# bxdrone.net
KiCad netlist of a schematic drawn in EAGLE
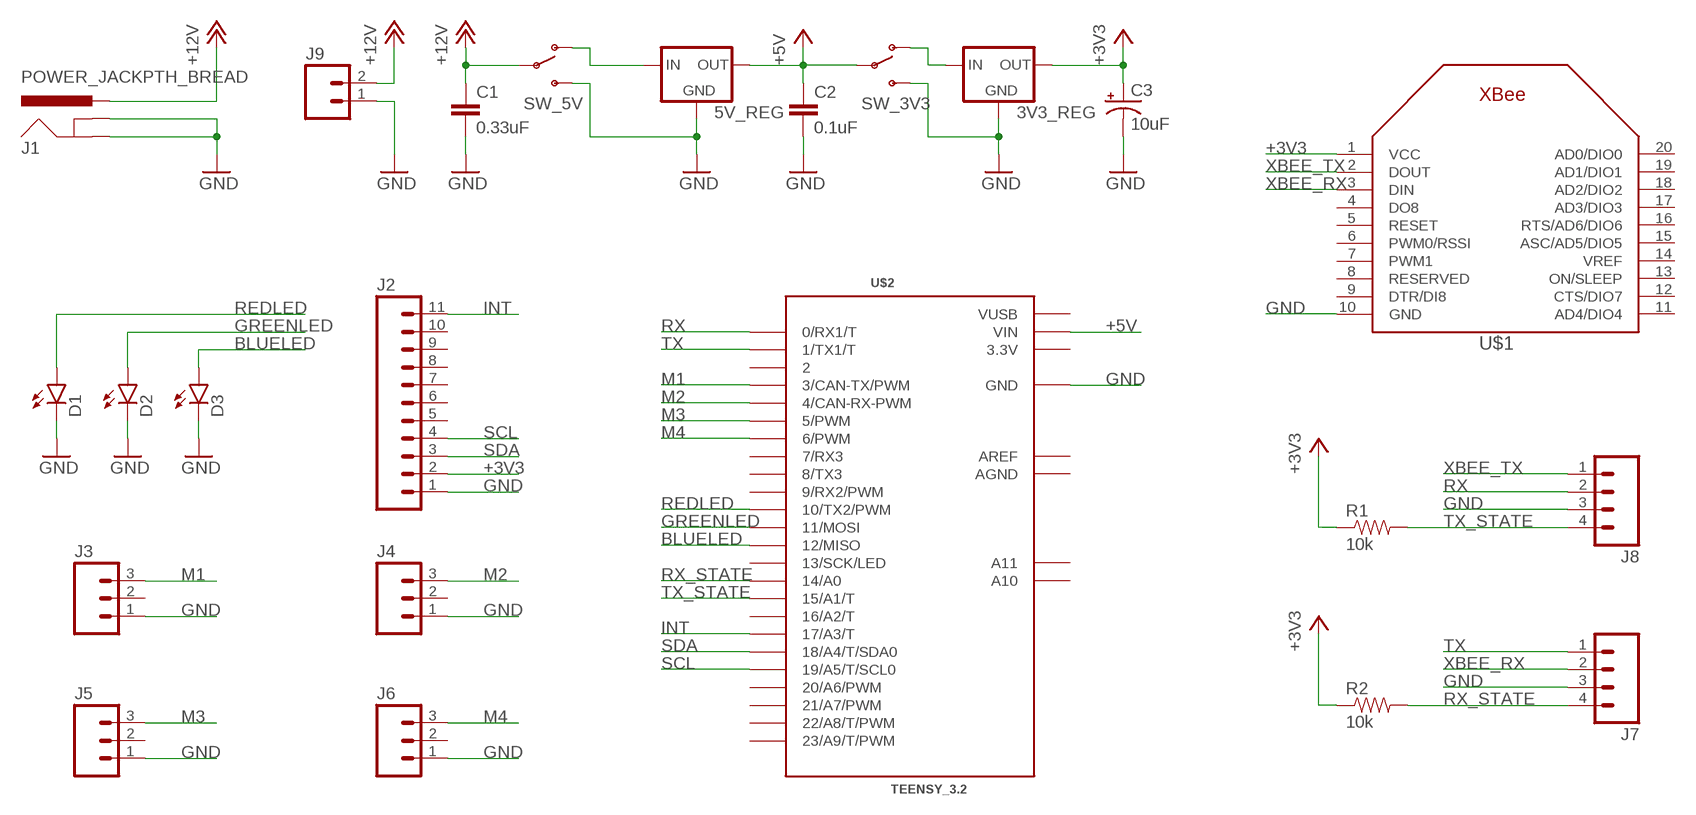
[diagram p0: schematic, sheet 1]

(export (version "E")
  (design (tool "Eeschema 10.0.6"))
  (components
    (comp (ref "3V3_REG")
      (value "LD1117V33")
      (footprint "eagle-import:TO-220-STANDING")
      (fields (field (name "MANUFACTURER") "ST Microelectronics"))
      (libsource (lib "eagle-import") (part "LD1117V33"))
    )
    (comp (ref "5V_REG")
      (value "L78S05CV")
      (footprint "eagle-import:TO-220-STANDING")
      (fields (field (name "MANUFACTURER") "St Microelectronics"))
      (libsource (lib "eagle-import") (part "L78S05CV"))
    )
    (comp (ref "C1")
      (value "0.33uF")
      (footprint "eagle-import:CAP-PTH-SMALL")
      (libsource (lib "eagle-import") (part "CAPPTH"))
    )
    (comp (ref "C2")
      (value "0.1uF")
      (footprint "eagle-import:CAP-PTH-SMALL")
      (libsource (lib "eagle-import") (part "CAPPTH"))
    )
    (comp (ref "C3")
      (value "10uF")
      (footprint "eagle-import:CPOL-RADIAL-10UF-25V")
      (libsource (lib "eagle-import") (part "CAP_POLPTH2"))
    )
    (comp (ref "D1")
      (value "LED5MM")
      (footprint "eagle-import:LED5MM")
      (libsource (lib "eagle-import") (part "LED5MM"))
    )
    (comp (ref "D2")
      (value "LED5MM")
      (footprint "eagle-import:LED5MM")
      (libsource (lib "eagle-import") (part "LED5MM"))
    )
    (comp (ref "D3")
      (value "LED5MM")
      (footprint "eagle-import:LED5MM")
      (libsource (lib "eagle-import") (part "LED5MM"))
    )
    (comp (ref "J1")
      (value "POWER_JACKPTH_BREAD")
      (footprint "eagle-import:POWER_JACK_PTH_BREAD")
      (libsource (lib "eagle-import") (part "POWER_JACKPTH_BREAD"))
    )
    (comp (ref "J2")
      (value "M11PTH")
      (footprint "eagle-import:1X11")
      (libsource (lib "eagle-import") (part "M11PTH"))
    )
    (comp (ref "J3")
      (value "M03PTH")
      (footprint "eagle-import:1X03")
      (libsource (lib "eagle-import") (part "M03PTH"))
    )
    (comp (ref "J4")
      (value "M03PTH")
      (footprint "eagle-import:1X03")
      (libsource (lib "eagle-import") (part "M03PTH"))
    )
    (comp (ref "J5")
      (value "M03PTH")
      (footprint "eagle-import:1X03")
      (libsource (lib "eagle-import") (part "M03PTH"))
    )
    (comp (ref "J6")
      (value "M03PTH")
      (footprint "eagle-import:1X03")
      (libsource (lib "eagle-import") (part "M03PTH"))
    )
    (comp (ref "J7")
      (value "M04PTH")
      (footprint "eagle-import:1X04")
      (libsource (lib "eagle-import") (part "M04PTH"))
    )
    (comp (ref "J8")
      (value "M04PTH")
      (footprint "eagle-import:1X04")
      (libsource (lib "eagle-import") (part "M04PTH"))
    )
    (comp (ref "J9")
      (value "M02JST-PTH-VERT")
      (footprint "eagle-import:JST-2-PTH-VERT")
      (libsource (lib "eagle-import") (part "M02JST-PTH-VERT"))
    )
    (comp (ref "R1")
      (value "10k")
      (footprint "eagle-import:AXIAL-0.4")
      (libsource (lib "eagle-import") (part "RESISTORPTH-1/4W"))
    )
    (comp (ref "R2")
      (value "10k")
      (footprint "eagle-import:AXIAL-0.4")
      (libsource (lib "eagle-import") (part "RESISTORPTH-1/4W"))
    )
    (comp (ref "SW_3V3")
      (value "SWITCH-SPDTPTH")
      (footprint "eagle-import:SWITCH-SPDT")
      (libsource (lib "eagle-import") (part "SWITCH-SPDTPTH"))
    )
    (comp (ref "SW_5V")
      (value "SWITCH-SPDTPTH")
      (footprint "eagle-import:SWITCH-SPDT")
      (libsource (lib "eagle-import") (part "SWITCH-SPDTPTH"))
    )
    (comp (ref "U$1")
      (value "XBEE")
      (footprint "eagle-import:XBEE")
      (libsource (lib "eagle-import") (part "XBEE"))
    )
    (comp (ref "U$2")
      (value "TEENSY_3.2")
      (footprint "eagle-import:TEENSY3-DIL+4")
      (libsource (lib "eagle-import") (part "TEENSY_3.1_DIL+4"))
    )
  )
  (nets
    (net (code "1") (name "+3V3") (class "Default")
      (node (ref "3V3_REG") (pin "2") (pinfunction "OUT_2") (pintype "passive"))
      (node (ref "C3") (pin "1") (pinfunction "+_1") (pintype "passive"))
      (node (ref "J2") (pin "2") (pinfunction "2_2") (pintype "passive"))
      (node (ref "R1") (pin "P$1") (pinfunction "1_P$1") (pintype "passive"))
      (node (ref "R2") (pin "P$1") (pinfunction "1_P$1") (pintype "passive"))
      (node (ref "U$1") (pin "1") (pinfunction "VCC_1") (pintype "power_in"))
    )
    (net (code "2") (name "+5V") (class "Default")
      (node (ref "5V_REG") (pin "3") (pinfunction "OUT_3") (pintype "passive"))
      (node (ref "C2") (pin "1") (pinfunction "1_1") (pintype "passive"))
      (node (ref "SW_3V3") (pin "2") (pinfunction "P_2") (pintype "passive"))
      (node (ref "U$2") (pin "VIN") (pinfunction "VIN_VIN") (pintype "power_in"))
    )
    (net (code "3") (name "+12V") (class "Default")
      (node (ref "C1") (pin "1") (pinfunction "1_1") (pintype "passive"))
      (node (ref "J1") (pin "PWR") (pinfunction "PWR_PWR") (pintype "bidirectional"))
      (node (ref "J9") (pin "2") (pinfunction "2_2") (pintype "passive"))
      (node (ref "SW_5V") (pin "2") (pinfunction "P_2") (pintype "passive"))
    )
    (net (code "4") (name "/3.3V") (class "Default")
      (node (ref "U$2") (pin "3.3V") (pinfunction "3.3V_3.3V") (pintype "power_in"))
    )
    (net (code "5") (name "/AGND") (class "Default")
      (node (ref "U$2") (pin "AGND") (pinfunction "AGND_AGND") (pintype "power_in"))
    )
    (net (code "6") (name "/AREF") (class "Default")
      (node (ref "U$2") (pin "AREF") (pinfunction "AREF_AREF") (pintype "power_in"))
    )
    (net (code "7") (name "/BLUELED") (class "Default")
      (node (ref "D3") (pin "A") (pinfunction "A_A") (pintype "passive"))
      (node (ref "U$2") (pin "12") (pinfunction "12/MISO_12") (pintype "bidirectional"))
    )
    (net (code "8") (name "/GREENLED") (class "Default")
      (node (ref "D2") (pin "A") (pinfunction "A_A") (pintype "passive"))
      (node (ref "U$2") (pin "11") (pinfunction "11/MOSI_11") (pintype "bidirectional"))
    )
    (net (code "9") (name "/INT") (class "Default")
      (node (ref "J2") (pin "11") (pinfunction "11_11") (pintype "passive"))
      (node (ref "U$2") (pin "17/A3") (pinfunction "17/A3/T_17/A3") (pintype "bidirectional"))
    )
    (net (code "10") (name "/M1") (class "Default")
      (node (ref "J3") (pin "3") (pinfunction "3_3") (pintype "passive"))
      (node (ref "U$2") (pin "3") (pinfunction "3/CAN-TX/PWM_3") (pintype "bidirectional"))
    )
    (net (code "11") (name "/M2") (class "Default")
      (node (ref "J4") (pin "3") (pinfunction "3_3") (pintype "passive"))
      (node (ref "U$2") (pin "4") (pinfunction "4/CAN-RX-PWM_4") (pintype "bidirectional"))
    )
    (net (code "12") (name "/M3") (class "Default")
      (node (ref "J5") (pin "3") (pinfunction "3_3") (pintype "passive"))
      (node (ref "U$2") (pin "5") (pinfunction "5/PWM_5") (pintype "bidirectional"))
    )
    (net (code "13") (name "/M4") (class "Default")
      (node (ref "J6") (pin "3") (pinfunction "3_3") (pintype "passive"))
      (node (ref "U$2") (pin "6") (pinfunction "6/PWM_6") (pintype "bidirectional"))
    )
    (net (code "14") (name "/REDLED") (class "Default")
      (node (ref "D1") (pin "A") (pinfunction "A_A") (pintype "passive"))
      (node (ref "U$2") (pin "10") (pinfunction "10/TX2/PWM_10") (pintype "bidirectional"))
    )
    (net (code "15") (name "/RX") (class "Default")
      (node (ref "J8") (pin "2") (pinfunction "2_2") (pintype "passive"))
      (node (ref "U$2") (pin "0") (pinfunction "0/RX1/T_0") (pintype "bidirectional"))
    )
    (net (code "16") (name "/RX_STATE") (class "Default")
      (node (ref "J7") (pin "4") (pinfunction "4_4") (pintype "passive"))
      (node (ref "R2") (pin "P$2") (pinfunction "2_P$2") (pintype "passive"))
      (node (ref "U$2") (pin "14/A0") (pinfunction "14/A0_14/A0") (pintype "bidirectional"))
    )
    (net (code "17") (name "/SCL") (class "Default")
      (node (ref "J2") (pin "4") (pinfunction "4_4") (pintype "passive"))
      (node (ref "U$2") (pin "19/A5") (pinfunction "19/A5/T/SCL0_19/A5") (pintype "bidirectional"))
    )
    (net (code "18") (name "/SDA") (class "Default")
      (node (ref "J2") (pin "3") (pinfunction "3_3") (pintype "passive"))
      (node (ref "U$2") (pin "18/A4") (pinfunction "18/A4/T/SDA0_18/A4") (pintype "bidirectional"))
    )
    (net (code "19") (name "/TX") (class "Default")
      (node (ref "J7") (pin "1") (pinfunction "1_1") (pintype "passive"))
      (node (ref "U$2") (pin "1") (pinfunction "1/TX1/T_1") (pintype "bidirectional"))
    )
    (net (code "20") (name "/TX_STATE") (class "Default")
      (node (ref "J8") (pin "4") (pinfunction "4_4") (pintype "passive"))
      (node (ref "R1") (pin "P$2") (pinfunction "2_P$2") (pintype "passive"))
      (node (ref "U$2") (pin "15/A1") (pinfunction "15/A1/T_15/A1") (pintype "bidirectional"))
    )
    (net (code "21") (name "/VUSB") (class "Default")
      (node (ref "U$2") (pin "VUSB") (pinfunction "VUSB_VUSB") (pintype "power_in"))
    )
    (net (code "22") (name "/XBEE_RX") (class "Default")
      (node (ref "J7") (pin "2") (pinfunction "2_2") (pintype "passive"))
      (node (ref "U$1") (pin "3") (pinfunction "DIN_3") (pintype "input"))
    )
    (net (code "23") (name "/XBEE_TX") (class "Default")
      (node (ref "J8") (pin "1") (pinfunction "1_1") (pintype "passive"))
      (node (ref "U$1") (pin "2") (pinfunction "DOUT_2") (pintype "output"))
    )
    (net (code "24") (name "GND") (class "Default")
      (node (ref "3V3_REG") (pin "1") (pinfunction "GND_1") (pintype "input"))
      (node (ref "5V_REG") (pin "2") (pinfunction "GND_2") (pintype "input"))
      (node (ref "C1") (pin "2") (pinfunction "2_2") (pintype "passive"))
      (node (ref "C2") (pin "2") (pinfunction "2_2") (pintype "passive"))
      (node (ref "C3") (pin "2") (pinfunction "-_2") (pintype "passive"))
      (node (ref "D1") (pin "K") (pinfunction "C_K") (pintype "passive"))
      (node (ref "D2") (pin "K") (pinfunction "C_K") (pintype "passive"))
      (node (ref "D3") (pin "K") (pinfunction "C_K") (pintype "passive"))
      (node (ref "J1") (pin "GND") (pinfunction "GND_GND") (pintype "bidirectional"))
      (node (ref "J1") (pin "GNDBREAK") (pinfunction "GNDBREAK_GNDBREAK") (pintype "bidirectional"))
      (node (ref "J2") (pin "1") (pinfunction "1_1") (pintype "passive"))
      (node (ref "J3") (pin "1") (pinfunction "1_1") (pintype "passive"))
      (node (ref "J4") (pin "1") (pinfunction "1_1") (pintype "passive"))
      (node (ref "J5") (pin "1") (pinfunction "1_1") (pintype "passive"))
      (node (ref "J6") (pin "1") (pinfunction "1_1") (pintype "passive"))
      (node (ref "J7") (pin "3") (pinfunction "3_3") (pintype "passive"))
      (node (ref "J8") (pin "3") (pinfunction "3_3") (pintype "passive"))
      (node (ref "J9") (pin "1") (pinfunction "1_1") (pintype "passive"))
      (node (ref "SW_3V3") (pin "3") (pinfunction "S_3") (pintype "passive"))
      (node (ref "SW_5V") (pin "3") (pinfunction "S_3") (pintype "passive"))
      (node (ref "U$1") (pin "10") (pinfunction "GND_10") (pintype "power_in"))
      (node (ref "U$2") (pin "GND") (pinfunction "GND_GND") (pintype "power_in"))
    )
    (net (code "25") (name "Net-(3V3_REG-IN)") (class "Default")
      (node (ref "3V3_REG") (pin "3") (pinfunction "IN_3") (pintype "input"))
      (node (ref "SW_3V3") (pin "1") (pinfunction "O_1") (pintype "passive"))
    )
    (net (code "26") (name "Net-(5V_REG-IN)") (class "Default")
      (node (ref "5V_REG") (pin "1") (pinfunction "IN_1") (pintype "input"))
      (node (ref "SW_5V") (pin "1") (pinfunction "O_1") (pintype "passive"))
    )
    (net (code "27") (name "unconnected-(J2-Pad5)") (class "Default")
      (node (ref "J2") (pin "5") (pinfunction "5_5") (pintype "passive"))
    )
    (net (code "28") (name "unconnected-(J2-Pad6)") (class "Default")
      (node (ref "J2") (pin "6") (pinfunction "6_6") (pintype "passive"))
    )
    (net (code "29") (name "unconnected-(J2-Pad7)") (class "Default")
      (node (ref "J2") (pin "7") (pinfunction "7_7") (pintype "passive"))
    )
    (net (code "30") (name "unconnected-(J2-Pad8)") (class "Default")
      (node (ref "J2") (pin "8") (pinfunction "8_8") (pintype "passive"))
    )
    (net (code "31") (name "unconnected-(J2-Pad9)") (class "Default")
      (node (ref "J2") (pin "9") (pinfunction "9_9") (pintype "passive"))
    )
    (net (code "32") (name "unconnected-(J2-Pad10)") (class "Default")
      (node (ref "J2") (pin "10") (pinfunction "10_10") (pintype "passive"))
    )
    (net (code "33") (name "unconnected-(J3-Pad2)") (class "Default")
      (node (ref "J3") (pin "2") (pinfunction "2_2") (pintype "passive"))
    )
    (net (code "34") (name "unconnected-(J4-Pad2)") (class "Default")
      (node (ref "J4") (pin "2") (pinfunction "2_2") (pintype "passive"))
    )
    (net (code "35") (name "unconnected-(J5-Pad2)") (class "Default")
      (node (ref "J5") (pin "2") (pinfunction "2_2") (pintype "passive"))
    )
    (net (code "36") (name "unconnected-(J6-Pad2)") (class "Default")
      (node (ref "J6") (pin "2") (pinfunction "2_2") (pintype "passive"))
    )
    (net (code "37") (name "unconnected-(U$1-AD0{slash}DIO0-Pad20)") (class "Default")
      (node (ref "U$1") (pin "20") (pinfunction "AD0/DIO0_20") (pintype "bidirectional"))
    )
    (net (code "38") (name "unconnected-(U$1-AD1{slash}DIO1-Pad19)") (class "Default")
      (node (ref "U$1") (pin "19") (pinfunction "AD1/DIO1_19") (pintype "bidirectional"))
    )
    (net (code "39") (name "unconnected-(U$1-AD2{slash}DIO2-Pad18)") (class "Default")
      (node (ref "U$1") (pin "18") (pinfunction "AD2/DIO2_18") (pintype "bidirectional"))
    )
    (net (code "40") (name "unconnected-(U$1-AD3{slash}DIO3-Pad17)") (class "Default")
      (node (ref "U$1") (pin "17") (pinfunction "AD3/DIO3_17") (pintype "bidirectional"))
    )
    (net (code "41") (name "unconnected-(U$1-AD4{slash}DIO4-Pad11)") (class "Default")
      (node (ref "U$1") (pin "11") (pinfunction "AD4/DIO4_11") (pintype "bidirectional"))
    )
    (net (code "42") (name "unconnected-(U$1-ASC{slash}AD5{slash}DIO5-Pad15)") (class "Default")
      (node (ref "U$1") (pin "15") (pinfunction "ASC/AD5/DIO5_15") (pintype "bidirectional"))
    )
    (net (code "43") (name "unconnected-(U$1-CTS{slash}DIO7-Pad12)") (class "Default")
      (node (ref "U$1") (pin "12") (pinfunction "CTS/DIO7_12") (pintype "bidirectional"))
    )
    (net (code "44") (name "unconnected-(U$1-DO8-Pad4)") (class "Default")
      (node (ref "U$1") (pin "4") (pinfunction "DO8_4") (pintype "output"))
    )
    (net (code "45") (name "unconnected-(U$1-DTR{slash}DI8-Pad9)") (class "Default")
      (node (ref "U$1") (pin "9") (pinfunction "DTR/DI8_9") (pintype "input"))
    )
    (net (code "46") (name "unconnected-(U$1-ON{slash}SLEEP-Pad13)") (class "Default")
      (node (ref "U$1") (pin "13") (pinfunction "ON/SLEEP_13") (pintype "output"))
    )
    (net (code "47") (name "unconnected-(U$1-PWM0{slash}RSSI-Pad6)") (class "Default")
      (node (ref "U$1") (pin "6") (pinfunction "PWM0/RSSI_6") (pintype "output"))
    )
    (net (code "48") (name "unconnected-(U$1-PWM1-Pad7)") (class "Default")
      (node (ref "U$1") (pin "7") (pinfunction "PWM1_7") (pintype "output"))
    )
    (net (code "49") (name "unconnected-(U$1-RESERVED-Pad8)") (class "Default")
      (node (ref "U$1") (pin "8") (pinfunction "RESERVED_8") (pintype "no_connect"))
    )
    (net (code "50") (name "unconnected-(U$1-RESET-Pad5)") (class "Default")
      (node (ref "U$1") (pin "5") (pinfunction "RESET_5") (pintype "input"))
    )
    (net (code "51") (name "unconnected-(U$1-RTS{slash}AD6{slash}DIO6-Pad16)") (class "Default")
      (node (ref "U$1") (pin "16") (pinfunction "RTS/AD6/DIO6_16") (pintype "bidirectional"))
    )
    (net (code "52") (name "unconnected-(U$1-VREF-Pad14)") (class "Default")
      (node (ref "U$1") (pin "14") (pinfunction "VREF_14") (pintype "input"))
    )
    (net (code "53") (name "unconnected-(U$2-7{slash}RX3-Pad7)") (class "Default")
      (node (ref "U$2") (pin "7") (pinfunction "7/RX3_7") (pintype "bidirectional"))
    )
    (net (code "54") (name "unconnected-(U$2-8{slash}TX3-Pad8)") (class "Default")
      (node (ref "U$2") (pin "8") (pinfunction "8/TX3_8") (pintype "bidirectional"))
    )
    (net (code "55") (name "unconnected-(U$2-9{slash}RX2{slash}PWM-Pad9)") (class "Default")
      (node (ref "U$2") (pin "9") (pinfunction "9/RX2/PWM_9") (pintype "bidirectional"))
    )
    (net (code "56") (name "unconnected-(U$2-13{slash}SCK{slash}LED-Pad13)") (class "Default")
      (node (ref "U$2") (pin "13") (pinfunction "13/SCK/LED_13") (pintype "bidirectional"))
    )
    (net (code "57") (name "unconnected-(U$2-16{slash}A2{slash}T-Pad16{slash}A2)") (class "Default")
      (node (ref "U$2") (pin "16/A2") (pinfunction "16/A2/T_16/A2") (pintype "bidirectional"))
    )
    (net (code "58") (name "unconnected-(U$2-20{slash}A6{slash}PWM-Pad20{slash}A6)") (class "Default")
      (node (ref "U$2") (pin "20/A6") (pinfunction "20/A6/PWM_20/A6") (pintype "bidirectional"))
    )
    (net (code "59") (name "unconnected-(U$2-21{slash}A7{slash}PWM-Pad21{slash}A7)") (class "Default")
      (node (ref "U$2") (pin "21/A7") (pinfunction "21/A7/PWM_21/A7") (pintype "bidirectional"))
    )
    (net (code "60") (name "unconnected-(U$2-22{slash}A8{slash}T{slash}PWM-Pad22{slash}A8)") (class "Default")
      (node (ref "U$2") (pin "22/A8") (pinfunction "22/A8/T/PWM_22/A8") (pintype "bidirectional"))
    )
    (net (code "61") (name "unconnected-(U$2-23{slash}A9{slash}T{slash}PWM-Pad23{slash}A9)") (class "Default")
      (node (ref "U$2") (pin "23/A9") (pinfunction "23/A9/T/PWM_23/A9") (pintype "bidirectional"))
    )
    (net (code "62") (name "unconnected-(U$2-Pad2)") (class "Default")
      (node (ref "U$2") (pin "2") (pinfunction "2_2") (pintype "bidirectional"))
    )
    (net (code "63") (name "unconnected-(U$2-PadA10)") (class "Default")
      (node (ref "U$2") (pin "A10") (pinfunction "A10_A10") (pintype "bidirectional"))
    )
    (net (code "64") (name "unconnected-(U$2-PadA11)") (class "Default")
      (node (ref "U$2") (pin "A11") (pinfunction "A11_A11") (pintype "bidirectional"))
    )
  )
)
